# eva01_connectors.net
KiCad netlist of a schematic drawn in Altium Designer
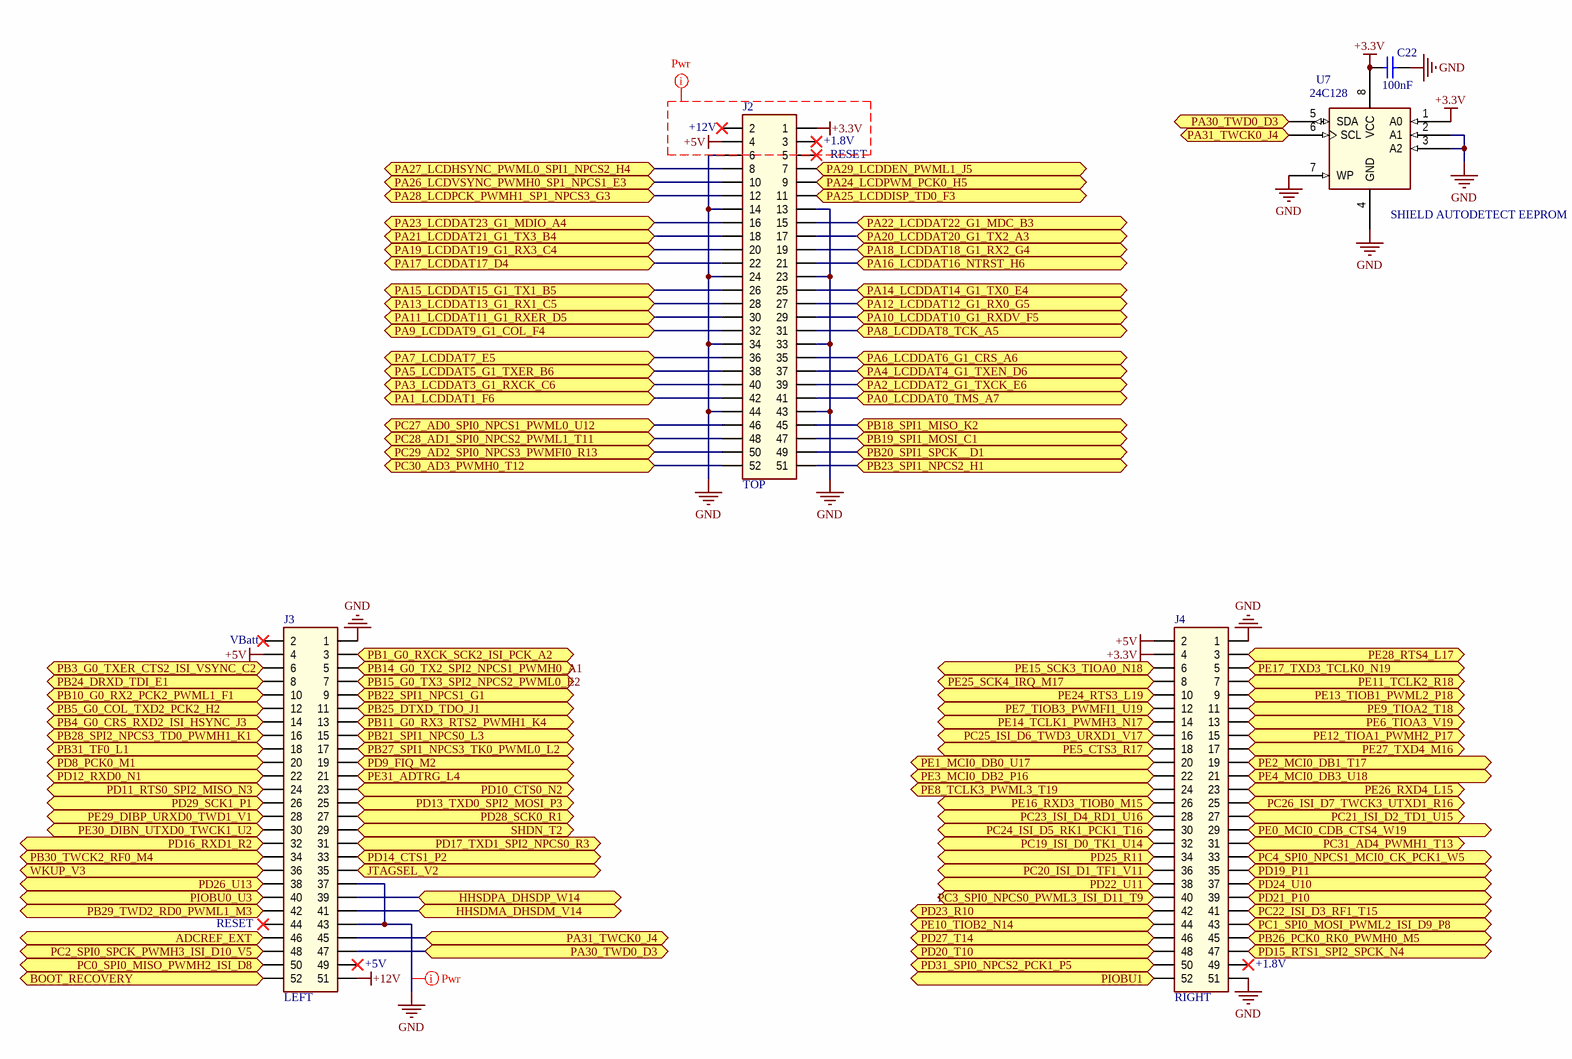
[diagram p0: eva01_connectors.SchDoc]

(export (version "E")
  (design (tool "Eeschema 10.0.6"))
  (components
    (comp (ref "C22")
      (value "100nF")
      (footprint "0603_[1608]")
      (description "Ceramic X7R 50V")
      (fields (field (name "PUBLISHER") "Altium Limited"))
      (libsource (lib "DEVELER_Library") (part "Cap"))
    )
    (comp (ref "J2")
      (value "TOP")
      (footprint "SOCKET_2x26_2.54MM_THD")
      (description "Socket Header, 52 pin, 26x2, 2.54mm, H=8.5mm")
      (fields (field (name "PART NUMBER") "Tyco 1-1634688"))
      (libsource (lib "DEVELER_Library") (part "Header 26x2"))
    )
    (comp (ref "J3")
      (value "LEFT")
      (footprint "SOCKET_2x26_2.54MM_THD")
      (description "Socket Header, 52 pin, 26x2, 2.54mm, H=8.5mm")
      (fields (field (name "PART NUMBER") "Tyco 1-1634688"))
      (libsource (lib "DEVELER_Library") (part "Header 26x2"))
    )
    (comp (ref "J4")
      (value "RIGHT")
      (footprint "SOCKET_2x26_2.54MM_THD")
      (description "Socket Header, 52 pin, 26x2, 2.54mm, H=8.5mm")
      (fields (field (name "PART NUMBER") "Tyco 1-1634688"))
      (libsource (lib "DEVELER_Library") (part "Header 26x2"))
    )
    (comp (ref "U7")
      (value "24C128")
      (footprint "SOIC8")
      (description "EEPROM")
      (libsource (lib "DEVELER_Library") (part "EEPROM-SOIC8"))
    )
  )
  (nets
    (net (code "1") (name "+3.3V") (class "Default")
      (node (ref "C22") (pin "2") (pinfunction "2_2") (pintype "passive"))
      (node (ref "J2") (pin "1") (pinfunction "1_1") (pintype "passive"))
      (node (ref "J4") (pin "4") (pinfunction "4_4") (pintype "passive"))
      (node (ref "U7") (pin "1") (pinfunction "A0_1") (pintype "input"))
      (node (ref "U7") (pin "8") (pinfunction "VCC_8") (pintype "power_in"))
    )
    (net (code "2") (name "+5V") (class "Default")
      (node (ref "J2") (pin "4") (pinfunction "4_4") (pintype "passive"))
      (node (ref "J3") (pin "4") (pinfunction "4_4") (pintype "passive"))
      (node (ref "J4") (pin "2") (pinfunction "2_2") (pintype "passive"))
    )
    (net (code "3") (name "+12V") (class "Default")
      (node (ref "J3") (pin "51") (pinfunction "51_51") (pintype "passive"))
    )
    (net (code "4") (name "/ADCREF_EXT") (class "Default")
      (node (ref "J3") (pin "46") (pinfunction "46_46") (pintype "passive"))
    )
    (net (code "5") (name "/BOOT_RECOVERY") (class "Default")
      (node (ref "J3") (pin "52") (pinfunction "52_52") (pintype "passive"))
    )
    (net (code "6") (name "/HHSDMA_DHSDM_V14") (class "Default")
      (node (ref "J3") (pin "41") (pinfunction "41_41") (pintype "passive"))
    )
    (net (code "7") (name "/HHSDPA_DHSDP_W14") (class "Default")
      (node (ref "J3") (pin "39") (pinfunction "39_39") (pintype "passive"))
    )
    (net (code "8") (name "/JTAGSEL_V2") (class "Default")
      (node (ref "J3") (pin "35") (pinfunction "35_35") (pintype "passive"))
    )
    (net (code "9") (name "/PA0_LCDDAT0_TMS_A7") (class "Default")
      (node (ref "J2") (pin "41") (pinfunction "41_41") (pintype "passive"))
    )
    (net (code "10") (name "/PA1_LCDDAT1_F6") (class "Default")
      (node (ref "J2") (pin "42") (pinfunction "42_42") (pintype "passive"))
    )
    (net (code "11") (name "/PA2_LCDDAT2_G1_TXCK_E6") (class "Default")
      (node (ref "J2") (pin "39") (pinfunction "39_39") (pintype "passive"))
    )
    (net (code "12") (name "/PA3_LCDDAT3_G1_RXCK_C6") (class "Default")
      (node (ref "J2") (pin "40") (pinfunction "40_40") (pintype "passive"))
    )
    (net (code "13") (name "/PA4_LCDDAT4_G1_TXEN_D6") (class "Default")
      (node (ref "J2") (pin "37") (pinfunction "37_37") (pintype "passive"))
    )
    (net (code "14") (name "/PA5_LCDDAT5_G1_TXER_B6") (class "Default")
      (node (ref "J2") (pin "38") (pinfunction "38_38") (pintype "passive"))
    )
    (net (code "15") (name "/PA6_LCDDAT6_G1_CRS_A6") (class "Default")
      (node (ref "J2") (pin "35") (pinfunction "35_35") (pintype "passive"))
    )
    (net (code "16") (name "/PA7_LCDDAT7_E5") (class "Default")
      (node (ref "J2") (pin "36") (pinfunction "36_36") (pintype "passive"))
    )
    (net (code "17") (name "/PA8_LCDDAT8_TCK_A5") (class "Default")
      (node (ref "J2") (pin "31") (pinfunction "31_31") (pintype "passive"))
    )
    (net (code "18") (name "/PA9_LCDDAT9_G1_COL_F4") (class "Default")
      (node (ref "J2") (pin "32") (pinfunction "32_32") (pintype "passive"))
    )
    (net (code "19") (name "/PA10_LCDDAT10_G1_RXDV_F5") (class "Default")
      (node (ref "J2") (pin "29") (pinfunction "29_29") (pintype "passive"))
    )
    (net (code "20") (name "/PA11_LCDDAT11_G1_RXER_D5") (class "Default")
      (node (ref "J2") (pin "30") (pinfunction "30_30") (pintype "passive"))
    )
    (net (code "21") (name "/PA12_LCDDAT12_G1_RX0_G5") (class "Default")
      (node (ref "J2") (pin "27") (pinfunction "27_27") (pintype "passive"))
    )
    (net (code "22") (name "/PA13_LCDDAT13_G1_RX1_C5") (class "Default")
      (node (ref "J2") (pin "28") (pinfunction "28_28") (pintype "passive"))
    )
    (net (code "23") (name "/PA14_LCDDAT14_G1_TX0_E4") (class "Default")
      (node (ref "J2") (pin "25") (pinfunction "25_25") (pintype "passive"))
    )
    (net (code "24") (name "/PA15_LCDDAT15_G1_TX1_B5") (class "Default")
      (node (ref "J2") (pin "26") (pinfunction "26_26") (pintype "passive"))
    )
    (net (code "25") (name "/PA16_LCDDAT16_NTRST_H6") (class "Default")
      (node (ref "J2") (pin "21") (pinfunction "21_21") (pintype "passive"))
    )
    (net (code "26") (name "/PA17_LCDDAT17_D4") (class "Default")
      (node (ref "J2") (pin "22") (pinfunction "22_22") (pintype "passive"))
    )
    (net (code "27") (name "/PA18_LCDDAT18_G1_RX2_G4") (class "Default")
      (node (ref "J2") (pin "19") (pinfunction "19_19") (pintype "passive"))
    )
    (net (code "28") (name "/PA19_LCDDAT19_G1_RX3_C4") (class "Default")
      (node (ref "J2") (pin "20") (pinfunction "20_20") (pintype "passive"))
    )
    (net (code "29") (name "/PA20_LCDDAT20_G1_TX2_A3") (class "Default")
      (node (ref "J2") (pin "17") (pinfunction "17_17") (pintype "passive"))
    )
    (net (code "30") (name "/PA21_LCDDAT21_G1_TX3_B4") (class "Default")
      (node (ref "J2") (pin "18") (pinfunction "18_18") (pintype "passive"))
    )
    (net (code "31") (name "/PA22_LCDDAT22_G1_MDC_B3") (class "Default")
      (node (ref "J2") (pin "15") (pinfunction "15_15") (pintype "passive"))
    )
    (net (code "32") (name "/PA23_LCDDAT23_G1_MDIO_A4") (class "Default")
      (node (ref "J2") (pin "16") (pinfunction "16_16") (pintype "passive"))
    )
    (net (code "33") (name "/PA24_LCDPWM_PCK0_H5") (class "Default")
      (node (ref "J2") (pin "9") (pinfunction "9_9") (pintype "passive"))
    )
    (net (code "34") (name "/PA25_LCDDISP_TD0_F3") (class "Default")
      (node (ref "J2") (pin "11") (pinfunction "11_11") (pintype "passive"))
    )
    (net (code "35") (name "/PA26_LCDVSYNC_PWMH0_SP1_NPCS1_E3") (class "Default")
      (node (ref "J2") (pin "10") (pinfunction "10_10") (pintype "passive"))
    )
    (net (code "36") (name "/PA27_LCDHSYNC_PWML0_SPI1_NPCS2_H4") (class "Default")
      (node (ref "J2") (pin "8") (pinfunction "8_8") (pintype "passive"))
    )
    (net (code "37") (name "/PA28_LCDPCK_PWMH1_SP1_NPCS3_G3") (class "Default")
      (node (ref "J2") (pin "12") (pinfunction "12_12") (pintype "passive"))
    )
    (net (code "38") (name "/PA29_LCDDEN_PWML1_J5") (class "Default")
      (node (ref "J2") (pin "7") (pinfunction "7_7") (pintype "passive"))
    )
    (net (code "39") (name "/PA30_TWD0_D3") (class "Default")
      (node (ref "J3") (pin "47") (pinfunction "47_47") (pintype "passive"))
      (node (ref "U7") (pin "5") (pinfunction "SDA_5") (pintype "bidirectional"))
    )
    (net (code "40") (name "/PA31_TWCK0_J4") (class "Default")
      (node (ref "J3") (pin "45") (pinfunction "45_45") (pintype "passive"))
      (node (ref "U7") (pin "6") (pinfunction "SCL_6") (pintype "input"))
    )
    (net (code "41") (name "/PB1_G0_RXCK_SCK2_ISI_PCK_A2") (class "Default")
      (node (ref "J3") (pin "3") (pinfunction "3_3") (pintype "passive"))
    )
    (net (code "42") (name "/PB3_G0_TXER_CTS2_ISI_VSYNC_C2") (class "Default")
      (node (ref "J3") (pin "6") (pinfunction "6_6") (pintype "passive"))
    )
    (net (code "43") (name "/PB4_G0_CRS_RXD2_ISI_HSYNC_J3") (class "Default")
      (node (ref "J3") (pin "14") (pinfunction "14_14") (pintype "passive"))
    )
    (net (code "44") (name "/PB5_G0_COL_TXD2_PCK2_H2") (class "Default")
      (node (ref "J3") (pin "12") (pinfunction "12_12") (pintype "passive"))
    )
    (net (code "45") (name "/PB10_G0_RX2_PCK2_PWML1_F1") (class "Default")
      (node (ref "J3") (pin "10") (pinfunction "10_10") (pintype "passive"))
    )
    (net (code "46") (name "/PB11_G0_RX3_RTS2_PWMH1_K4") (class "Default")
      (node (ref "J3") (pin "13") (pinfunction "13_13") (pintype "passive"))
    )
    (net (code "47") (name "/PB14_G0_TX2_SPI2_NPCS1_PWMH0_A1") (class "Default")
      (node (ref "J3") (pin "5") (pinfunction "5_5") (pintype "passive"))
    )
    (net (code "48") (name "/PB15_G0_TX3_SPI2_NPCS2_PWML0_E2") (class "Default")
      (node (ref "J3") (pin "7") (pinfunction "7_7") (pintype "passive"))
    )
    (net (code "49") (name "/PB18_SPI1_MISO_K2") (class "Default")
      (node (ref "J2") (pin "45") (pinfunction "45_45") (pintype "passive"))
    )
    (net (code "50") (name "/PB19_SPI1_MOSI_C1") (class "Default")
      (node (ref "J2") (pin "47") (pinfunction "47_47") (pintype "passive"))
    )
    (net (code "51") (name "/PB20_SPI1_SPCK__D1") (class "Default")
      (node (ref "J2") (pin "49") (pinfunction "49_49") (pintype "passive"))
    )
    (net (code "52") (name "/PB21_SPI1_NPCS0_L3") (class "Default")
      (node (ref "J3") (pin "15") (pinfunction "15_15") (pintype "passive"))
    )
    (net (code "53") (name "/PB22_SPI1_NPCS1_G1") (class "Default")
      (node (ref "J3") (pin "9") (pinfunction "9_9") (pintype "passive"))
    )
    (net (code "54") (name "/PB23_SPI1_NPCS2_H1") (class "Default")
      (node (ref "J2") (pin "51") (pinfunction "51_51") (pintype "passive"))
    )
    (net (code "55") (name "/PB24_DRXD_TDI_E1") (class "Default")
      (node (ref "J3") (pin "8") (pinfunction "8_8") (pintype "passive"))
    )
    (net (code "56") (name "/PB25_DTXD_TDO_J1") (class "Default")
      (node (ref "J3") (pin "11") (pinfunction "11_11") (pintype "passive"))
    )
    (net (code "57") (name "/PB26_PCK0_RK0_PWMH0_M5") (class "Default")
      (node (ref "J4") (pin "45") (pinfunction "45_45") (pintype "passive"))
    )
    (net (code "58") (name "/PB27_SPI1_NPCS3_TK0_PWML0_L2") (class "Default")
      (node (ref "J3") (pin "17") (pinfunction "17_17") (pintype "passive"))
    )
    (net (code "59") (name "/PB28_SPI2_NPCS3_TD0_PWMH1_K1") (class "Default")
      (node (ref "J3") (pin "16") (pinfunction "16_16") (pintype "passive"))
    )
    (net (code "60") (name "/PB29_TWD2_RD0_PWML1_M3") (class "Default")
      (node (ref "J3") (pin "42") (pinfunction "42_42") (pintype "passive"))
    )
    (net (code "61") (name "/PB30_TWCK2_RF0_M4") (class "Default")
      (node (ref "J3") (pin "34") (pinfunction "34_34") (pintype "passive"))
    )
    (net (code "62") (name "/PB31_TF0_L1") (class "Default")
      (node (ref "J3") (pin "18") (pinfunction "18_18") (pintype "passive"))
    )
    (net (code "63") (name "/PC0_SPI0_MISO_PWMH2_ISI_D8") (class "Default")
      (node (ref "J3") (pin "50") (pinfunction "50_50") (pintype "passive"))
    )
    (net (code "64") (name "/PC1_SPI0_MOSI_PWML2_ISI_D9_P8") (class "Default")
      (node (ref "J4") (pin "43") (pinfunction "43_43") (pintype "passive"))
    )
    (net (code "65") (name "/PC2_SPI0_SPCK_PWMH3_ISI_D10_V5") (class "Default")
      (node (ref "J3") (pin "48") (pinfunction "48_48") (pintype "passive"))
    )
    (net (code "66") (name "/PC3_SPI0_NPCS0_PWML3_ISI_D11_T9") (class "Default")
      (node (ref "J4") (pin "40") (pinfunction "40_40") (pintype "passive"))
    )
    (net (code "67") (name "/PC4_SPI0_NPCS1_MCI0_CK_PCK1_W5") (class "Default")
      (node (ref "J4") (pin "33") (pinfunction "33_33") (pintype "passive"))
    )
    (net (code "68") (name "/PC19_ISI_D0_TK1_U14") (class "Default")
      (node (ref "J4") (pin "32") (pinfunction "32_32") (pintype "passive"))
    )
    (net (code "69") (name "/PC20_ISI_D1_TF1_V11") (class "Default")
      (node (ref "J4") (pin "36") (pinfunction "36_36") (pintype "passive"))
    )
    (net (code "70") (name "/PC21_ISI_D2_TD1_U15") (class "Default")
      (node (ref "J4") (pin "27") (pinfunction "27_27") (pintype "passive"))
    )
    (net (code "71") (name "/PC22_ISI_D3_RF1_T15") (class "Default")
      (node (ref "J4") (pin "41") (pinfunction "41_41") (pintype "passive"))
    )
    (net (code "72") (name "/PC23_ISI_D4_RD1_U16") (class "Default")
      (node (ref "J4") (pin "28") (pinfunction "28_28") (pintype "passive"))
    )
    (net (code "73") (name "/PC24_ISI_D5_RK1_PCK1_T16") (class "Default")
      (node (ref "J4") (pin "30") (pinfunction "30_30") (pintype "passive"))
    )
    (net (code "74") (name "/PC25_ISI_D6_TWD3_URXD1_V17") (class "Default")
      (node (ref "J4") (pin "16") (pinfunction "16_16") (pintype "passive"))
    )
    (net (code "75") (name "/PC26_ISI_D7_TWCK3_UTXD1_R16") (class "Default")
      (node (ref "J4") (pin "25") (pinfunction "25_25") (pintype "passive"))
    )
    (net (code "76") (name "/PC27_AD0_SPI0_NPCS1_PWML0_U12") (class "Default")
      (node (ref "J2") (pin "46") (pinfunction "46_46") (pintype "passive"))
    )
    (net (code "77") (name "/PC28_AD1_SPI0_NPCS2_PWML1_T11") (class "Default")
      (node (ref "J2") (pin "48") (pinfunction "48_48") (pintype "passive"))
    )
    (net (code "78") (name "/PC29_AD2_SPI0_NPCS3_PWMFI0_R13") (class "Default")
      (node (ref "J2") (pin "50") (pinfunction "50_50") (pintype "passive"))
    )
    (net (code "79") (name "/PC30_AD3_PWMH0_T12") (class "Default")
      (node (ref "J2") (pin "52") (pinfunction "52_52") (pintype "passive"))
    )
    (net (code "80") (name "/PC31_AD4_PWMH1_T13") (class "Default")
      (node (ref "J4") (pin "31") (pinfunction "31_31") (pintype "passive"))
    )
    (net (code "81") (name "/PD8_PCK0_M1") (class "Default")
      (node (ref "J3") (pin "20") (pinfunction "20_20") (pintype "passive"))
    )
    (net (code "82") (name "/PD9_FIQ_M2") (class "Default")
      (node (ref "J3") (pin "19") (pinfunction "19_19") (pintype "passive"))
    )
    (net (code "83") (name "/PD10_CTS0_N2") (class "Default")
      (node (ref "J3") (pin "23") (pinfunction "23_23") (pintype "passive"))
    )
    (net (code "84") (name "/PD11_RTS0_SPI2_MISO_N3") (class "Default")
      (node (ref "J3") (pin "24") (pinfunction "24_24") (pintype "passive"))
    )
    (net (code "85") (name "/PD12_RXD0_N1") (class "Default")
      (node (ref "J3") (pin "22") (pinfunction "22_22") (pintype "passive"))
    )
    (net (code "86") (name "/PD13_TXD0_SPI2_MOSI_P3") (class "Default")
      (node (ref "J3") (pin "25") (pinfunction "25_25") (pintype "passive"))
    )
    (net (code "87") (name "/PD14_CTS1_P2") (class "Default")
      (node (ref "J3") (pin "33") (pinfunction "33_33") (pintype "passive"))
    )
    (net (code "88") (name "/PD15_RTS1_SPI2_SPCK_N4") (class "Default")
      (node (ref "J4") (pin "47") (pinfunction "47_47") (pintype "passive"))
    )
    (net (code "89") (name "/PD16_RXD1_R2") (class "Default")
      (node (ref "J3") (pin "32") (pinfunction "32_32") (pintype "passive"))
    )
    (net (code "90") (name "/PD17_TXD1_SPI2_NPCS0_R3") (class "Default")
      (node (ref "J3") (pin "31") (pinfunction "31_31") (pintype "passive"))
    )
    (net (code "91") (name "/PD19_P11") (class "Default")
      (node (ref "J4") (pin "35") (pinfunction "35_35") (pintype "passive"))
    )
    (net (code "92") (name "/PD20_T10") (class "Default")
      (node (ref "J4") (pin "48") (pinfunction "48_48") (pintype "passive"))
    )
    (net (code "93") (name "/PD21_P10") (class "Default")
      (node (ref "J4") (pin "39") (pinfunction "39_39") (pintype "passive"))
    )
    (net (code "94") (name "/PD22_U11") (class "Default")
      (node (ref "J4") (pin "38") (pinfunction "38_38") (pintype "passive"))
    )
    (net (code "95") (name "/PD23_R10") (class "Default")
      (node (ref "J4") (pin "42") (pinfunction "42_42") (pintype "passive"))
    )
    (net (code "96") (name "/PD24_U10") (class "Default")
      (node (ref "J4") (pin "37") (pinfunction "37_37") (pintype "passive"))
    )
    (net (code "97") (name "/PD25_R11") (class "Default")
      (node (ref "J4") (pin "34") (pinfunction "34_34") (pintype "passive"))
    )
    (net (code "98") (name "/PD26_U13") (class "Default")
      (node (ref "J3") (pin "38") (pinfunction "38_38") (pintype "passive"))
    )
    (net (code "99") (name "/PD27_T14") (class "Default")
      (node (ref "J4") (pin "46") (pinfunction "46_46") (pintype "passive"))
    )
    (net (code "100") (name "/PD28_SCK0_R1") (class "Default")
      (node (ref "J3") (pin "27") (pinfunction "27_27") (pintype "passive"))
    )
    (net (code "101") (name "/PD29_SCK1_P1") (class "Default")
      (node (ref "J3") (pin "26") (pinfunction "26_26") (pintype "passive"))
    )
    (net (code "102") (name "/PD31_SPI0_NPCS2_PCK1_P5") (class "Default")
      (node (ref "J4") (pin "50") (pinfunction "50_50") (pintype "passive"))
    )
    (net (code "103") (name "/PE0_MCI0_CDB_CTS4_W19") (class "Default")
      (node (ref "J4") (pin "29") (pinfunction "29_29") (pintype "passive"))
    )
    (net (code "104") (name "/PE1_MCI0_DB0_U17") (class "Default")
      (node (ref "J4") (pin "20") (pinfunction "20_20") (pintype "passive"))
    )
    (net (code "105") (name "/PE2_MCI0_DB1_T17") (class "Default")
      (node (ref "J4") (pin "19") (pinfunction "19_19") (pintype "passive"))
    )
    (net (code "106") (name "/PE3_MCI0_DB2_P16") (class "Default")
      (node (ref "J4") (pin "22") (pinfunction "22_22") (pintype "passive"))
    )
    (net (code "107") (name "/PE4_MCI0_DB3_U18") (class "Default")
      (node (ref "J4") (pin "21") (pinfunction "21_21") (pintype "passive"))
    )
    (net (code "108") (name "/PE5_CTS3_R17") (class "Default")
      (node (ref "J4") (pin "18") (pinfunction "18_18") (pintype "passive"))
    )
    (net (code "109") (name "/PE6_TIOA3_V19") (class "Default")
      (node (ref "J4") (pin "13") (pinfunction "13_13") (pintype "passive"))
    )
    (net (code "110") (name "/PE7_TIOB3_PWMFI1_U19") (class "Default")
      (node (ref "J4") (pin "12") (pinfunction "12_12") (pintype "passive"))
    )
    (net (code "111") (name "/PE8_TCLK3_PWML3_T19") (class "Default")
      (node (ref "J4") (pin "24") (pinfunction "24_24") (pintype "passive"))
    )
    (net (code "112") (name "/PE9_TIOA2_T18") (class "Default")
      (node (ref "J4") (pin "11") (pinfunction "11_11") (pintype "passive"))
    )
    (net (code "113") (name "/PE10_TIOB2_N14") (class "Default")
      (node (ref "J4") (pin "44") (pinfunction "44_44") (pintype "passive"))
    )
    (net (code "114") (name "/PE11_TCLK2_R18") (class "Default")
      (node (ref "J4") (pin "7") (pinfunction "7_7") (pintype "passive"))
    )
    (net (code "115") (name "/PE12_TIOA1_PWMH2_P17") (class "Default")
      (node (ref "J4") (pin "15") (pinfunction "15_15") (pintype "passive"))
    )
    (net (code "116") (name "/PE13_TIOB1_PWML2_P18") (class "Default")
      (node (ref "J4") (pin "9") (pinfunction "9_9") (pintype "passive"))
    )
    (net (code "117") (name "/PE14_TCLK1_PWMH3_N17") (class "Default")
      (node (ref "J4") (pin "14") (pinfunction "14_14") (pintype "passive"))
    )
    (net (code "118") (name "/PE15_SCK3_TIOA0_N18") (class "Default")
      (node (ref "J4") (pin "6") (pinfunction "6_6") (pintype "passive"))
    )
    (net (code "119") (name "/PE16_RXD3_TIOB0_M15") (class "Default")
      (node (ref "J4") (pin "26") (pinfunction "26_26") (pintype "passive"))
    )
    (net (code "120") (name "/PE17_TXD3_TCLK0_N19") (class "Default")
      (node (ref "J4") (pin "5") (pinfunction "5_5") (pintype "passive"))
    )
    (net (code "121") (name "/PE24_RTS3_L19") (class "Default")
      (node (ref "J4") (pin "10") (pinfunction "10_10") (pintype "passive"))
    )
    (net (code "122") (name "/PE25_SCK4_IRQ_M17") (class "Default")
      (node (ref "J4") (pin "8") (pinfunction "8_8") (pintype "passive"))
    )
    (net (code "123") (name "/PE26_RXD4_L15") (class "Default")
      (node (ref "J4") (pin "23") (pinfunction "23_23") (pintype "passive"))
    )
    (net (code "124") (name "/PE27_TXD4_M16") (class "Default")
      (node (ref "J4") (pin "17") (pinfunction "17_17") (pintype "passive"))
    )
    (net (code "125") (name "/PE28_RTS4_L17") (class "Default")
      (node (ref "J4") (pin "3") (pinfunction "3_3") (pintype "passive"))
    )
    (net (code "126") (name "/PE29_DIBP_URXD0_TWD1_V1") (class "Default")
      (node (ref "J3") (pin "28") (pinfunction "28_28") (pintype "passive"))
    )
    (net (code "127") (name "/PE30_DIBN_UTXD0_TWCK1_U2") (class "Default")
      (node (ref "J3") (pin "30") (pinfunction "30_30") (pintype "passive"))
    )
    (net (code "128") (name "/PE31_ADTRG_L4") (class "Default")
      (node (ref "J3") (pin "21") (pinfunction "21_21") (pintype "passive"))
    )
    (net (code "129") (name "/PIOBU0_U3") (class "Default")
      (node (ref "J3") (pin "40") (pinfunction "40_40") (pintype "passive"))
    )
    (net (code "130") (name "/PIOBU1") (class "Default")
      (node (ref "J4") (pin "52") (pinfunction "52_52") (pintype "passive"))
    )
    (net (code "131") (name "/SHDN_T2") (class "Default")
      (node (ref "J3") (pin "29") (pinfunction "29_29") (pintype "passive"))
    )
    (net (code "132") (name "/WKUP_V3") (class "Default")
      (node (ref "J3") (pin "36") (pinfunction "36_36") (pintype "passive"))
    )
    (net (code "133") (name "GND") (class "Default")
      (node (ref "C22") (pin "1") (pinfunction "1_1") (pintype "passive"))
      (node (ref "J2") (pin "13") (pinfunction "13_13") (pintype "passive"))
      (node (ref "J2") (pin "14") (pinfunction "14_14") (pintype "passive"))
      (node (ref "J2") (pin "23") (pinfunction "23_23") (pintype "passive"))
      (node (ref "J2") (pin "24") (pinfunction "24_24") (pintype "passive"))
      (node (ref "J2") (pin "33") (pinfunction "33_33") (pintype "passive"))
      (node (ref "J2") (pin "34") (pinfunction "34_34") (pintype "passive"))
      (node (ref "J2") (pin "43") (pinfunction "43_43") (pintype "passive"))
      (node (ref "J2") (pin "44") (pinfunction "44_44") (pintype "passive"))
      (node (ref "J2") (pin "6") (pinfunction "6_6") (pintype "passive"))
      (node (ref "J3") (pin "1") (pinfunction "1_1") (pintype "passive"))
      (node (ref "J3") (pin "37") (pinfunction "37_37") (pintype "passive"))
      (node (ref "J3") (pin "43") (pinfunction "43_43") (pintype "passive"))
      (node (ref "J4") (pin "1") (pinfunction "1_1") (pintype "passive"))
      (node (ref "J4") (pin "51") (pinfunction "51_51") (pintype "passive"))
      (node (ref "U7") (pin "2") (pinfunction "A1_2") (pintype "input"))
      (node (ref "U7") (pin "3") (pinfunction "A2_3") (pintype "input"))
      (node (ref "U7") (pin "4") (pinfunction "GND_4") (pintype "power_in"))
      (node (ref "U7") (pin "7") (pinfunction "WP_7") (pintype "input"))
    )
    (net (code "134") (name "unconnected-(J2-Pad2)") (class "Default")
      (node (ref "J2") (pin "2") (pinfunction "2_2") (pintype "passive+no_connect"))
    )
    (net (code "135") (name "unconnected-(J2-Pad3)") (class "Default")
      (node (ref "J2") (pin "3") (pinfunction "3_3") (pintype "passive+no_connect"))
    )
    (net (code "136") (name "unconnected-(J2-Pad5)") (class "Default")
      (node (ref "J2") (pin "5") (pinfunction "5_5") (pintype "passive+no_connect"))
    )
    (net (code "137") (name "unconnected-(J3-Pad2)") (class "Default")
      (node (ref "J3") (pin "2") (pinfunction "2_2") (pintype "passive+no_connect"))
    )
    (net (code "138") (name "unconnected-(J3-Pad44)") (class "Default")
      (node (ref "J3") (pin "44") (pinfunction "44_44") (pintype "passive+no_connect"))
    )
    (net (code "139") (name "unconnected-(J3-Pad49)") (class "Default")
      (node (ref "J3") (pin "49") (pinfunction "49_49") (pintype "passive+no_connect"))
    )
    (net (code "140") (name "unconnected-(J4-Pad49)") (class "Default")
      (node (ref "J4") (pin "49") (pinfunction "49_49") (pintype "passive+no_connect"))
    )
  )
)
